# Adafruit_96x64_RGB_OLED_Breakout.net
KiCad netlist of a schematic drawn in EAGLE
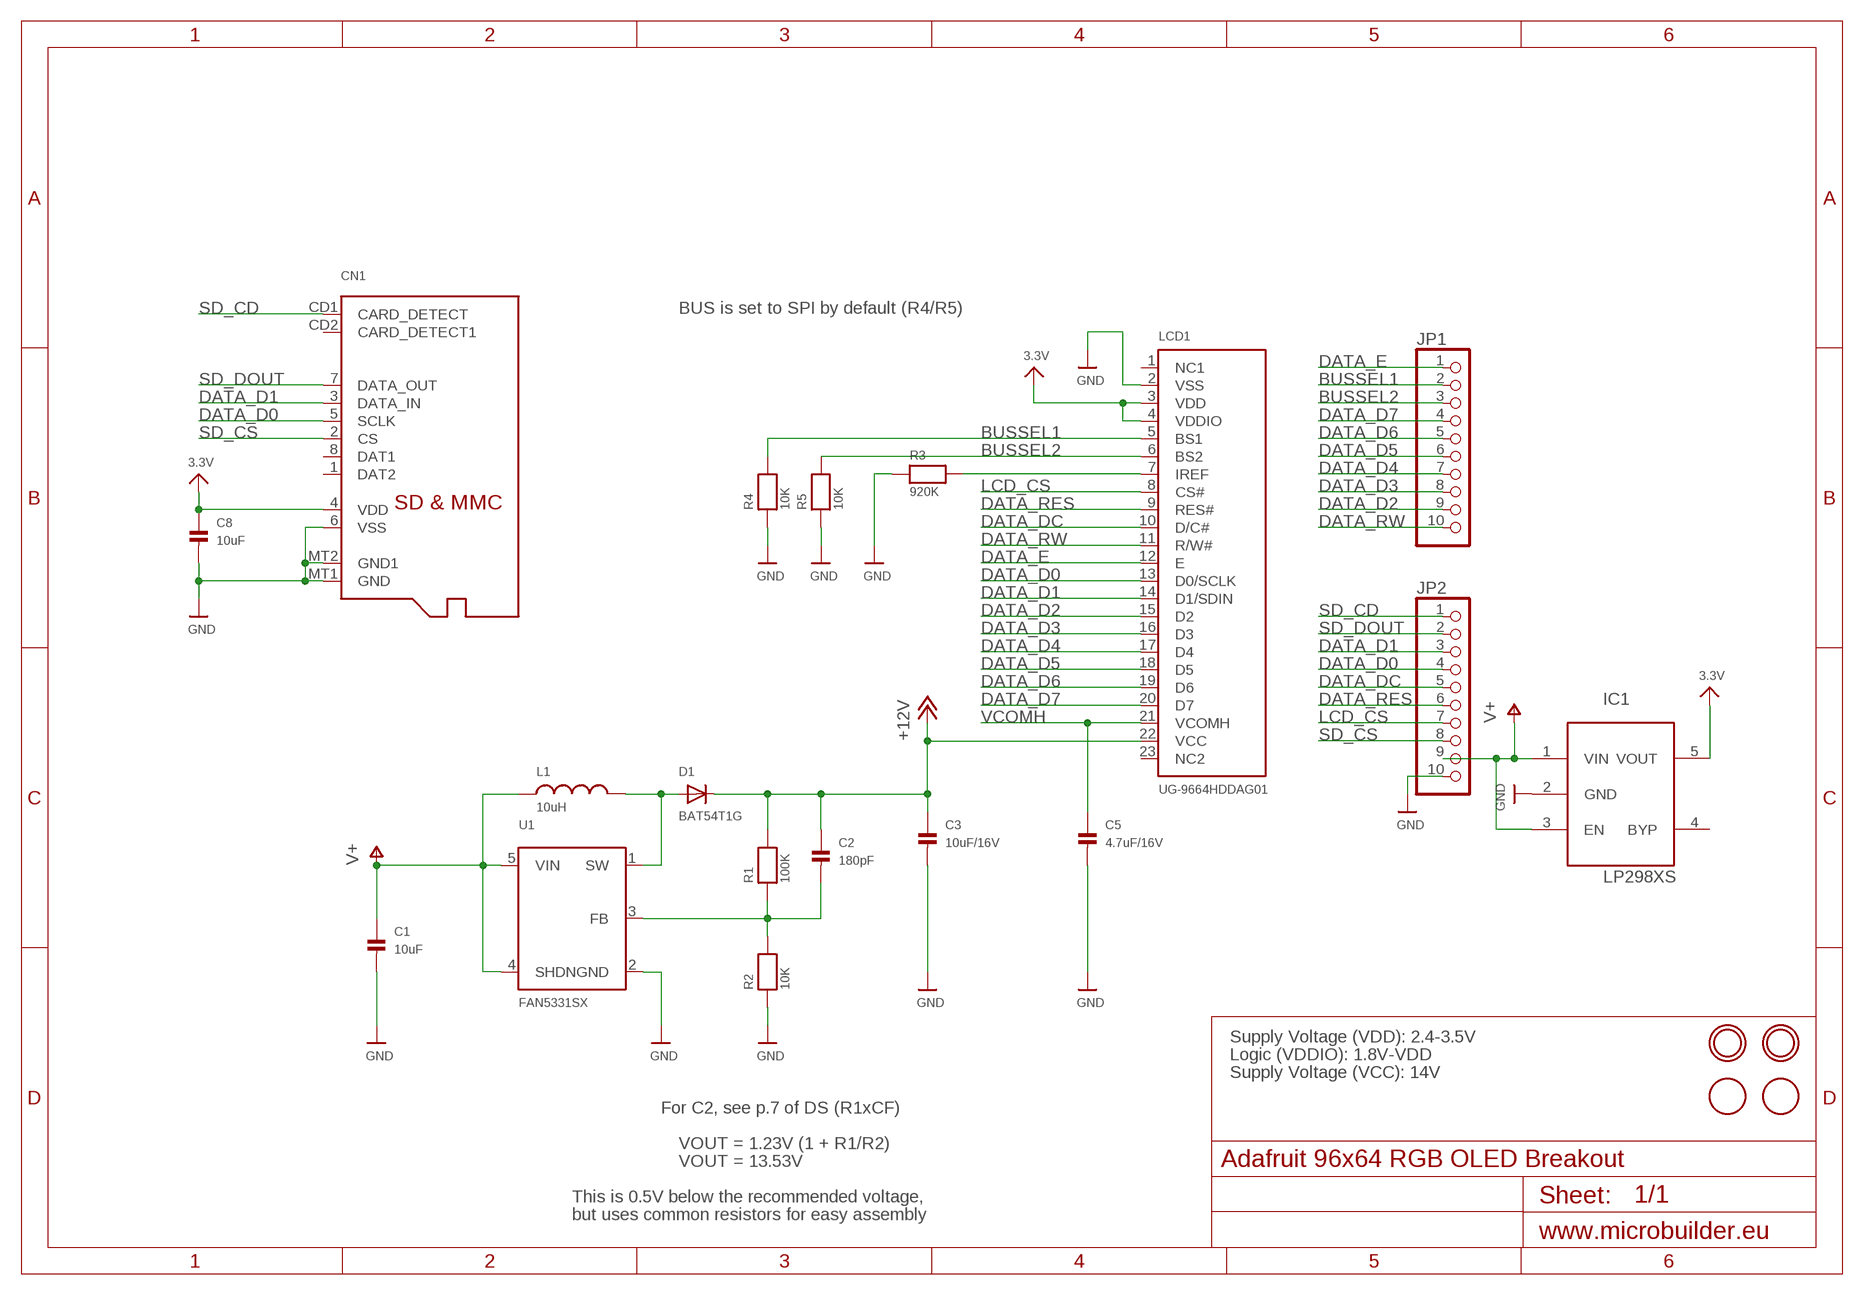
[diagram p0: schematic, sheet 1]

(export (version "E")
  (design (tool "Eeschema 10.0.6"))
  (components
    (comp (ref "C1")
      (value "10uF")
      (footprint "eagle-import:0805")
      (libsource (lib "eagle-import") (part "CAP_CERAMIC0805"))
    )
    (comp (ref "C2")
      (value "180pF")
      (footprint "eagle-import:0805")
      (libsource (lib "eagle-import") (part "CAP_CERAMIC0805"))
    )
    (comp (ref "C3")
      (value "10uF/16V")
      (footprint "eagle-import:0805")
      (libsource (lib "eagle-import") (part "CAP_CERAMIC0805"))
    )
    (comp (ref "C5")
      (value "4.7uF/16V")
      (footprint "eagle-import:0805")
      (libsource (lib "eagle-import") (part "CAP_CERAMIC0805"))
    )
    (comp (ref "C8")
      (value "10uF")
      (footprint "eagle-import:0805")
      (libsource (lib "eagle-import") (part "CAP_CERAMIC0805"))
    )
    (comp (ref "CN1")
      (value "MICROSD")
      (footprint "eagle-import:MICROSD")
      (libsource (lib "eagle-import") (part "MICROSD"))
    )
    (comp (ref "D1")
      (value "BAT54T1G")
      (footprint "eagle-import:SOD-123")
      (libsource (lib "eagle-import") (part "DIODESOD-123"))
    )
    (comp (ref "IC1")
      (value "LP298XS")
      (footprint "eagle-import:SOT23-5L")
      (libsource (lib "eagle-import") (part "LP298XS"))
    )
    (comp (ref "JP1")
      (value "HEADER-1X10THICKER")
      (footprint "eagle-import:1X10_ROUND_76")
      (libsource (lib "eagle-import") (part "HEADER-1X10THICKER"))
    )
    (comp (ref "JP2")
      (value "HEADER-1X10THICKER")
      (footprint "eagle-import:1X10_ROUND_76")
      (libsource (lib "eagle-import") (part "HEADER-1X10THICKER"))
    )
    (comp (ref "L1")
      (value "10uH")
      (footprint "eagle-import:INDUCTOR_1007")
      (libsource (lib "eagle-import") (part "INDUCTOR"))
    )
    (comp (ref "LCD1")
      (value "UG-9664HDDAG01")
      (footprint "eagle-import:UG-9664HDDAG01_WRAPAROUND")
      (libsource (lib "eagle-import") (part "OLED_UG-9664HDDAG01WRAPAROUND"))
    )
    (comp (ref "R1")
      (value "100K")
      (footprint "eagle-import:0805")
      (libsource (lib "eagle-import") (part "RESISTOR0805"))
    )
    (comp (ref "R2")
      (value "10K")
      (footprint "eagle-import:0805")
      (libsource (lib "eagle-import") (part "RESISTOR0805"))
    )
    (comp (ref "R3")
      (value "920K")
      (footprint "eagle-import:0805")
      (libsource (lib "eagle-import") (part "RESISTOR0805"))
    )
    (comp (ref "R4")
      (value "10K")
      (footprint "eagle-import:0805")
      (libsource (lib "eagle-import") (part "RESISTOR0805"))
    )
    (comp (ref "R5")
      (value "10K")
      (footprint "eagle-import:0805")
      (libsource (lib "eagle-import") (part "RESISTOR0805"))
    )
    (comp (ref "U$9")
      (value "MOUNTINGHOLE2.0")
      (footprint "eagle-import:MOUNTINGHOLE_2.0_PLATED")
      (libsource (lib "eagle-import") (part "MOUNTINGHOLE2.0"))
    )
    (comp (ref "U$11")
      (value "MOUNTINGHOLE2.0")
      (footprint "eagle-import:MOUNTINGHOLE_2.0_PLATED")
      (libsource (lib "eagle-import") (part "MOUNTINGHOLE2.0"))
    )
    (comp (ref "U$12")
      (value "FIDUCIAL")
      (footprint "eagle-import:FIDUCIAL_1MM")
      (libsource (lib "eagle-import") (part "FIDUCIAL"))
    )
    (comp (ref "U$13")
      (value "FIDUCIAL")
      (footprint "eagle-import:FIDUCIAL_1MM")
      (libsource (lib "eagle-import") (part "FIDUCIAL"))
    )
    (comp (ref "U1")
      (value "FAN5331SX")
      (footprint "eagle-import:SOT23-5")
      (libsource (lib "eagle-import") (part "FAN5331"))
    )
  )
  (nets
    (net (code "1") (name "+12V") (class "Default")
      (node (ref "C2") (pin "1") (pinfunction "P$1_1") (pintype "passive"))
      (node (ref "C3") (pin "1") (pinfunction "P$1_1") (pintype "passive"))
      (node (ref "D1") (pin "C") (pinfunction "C_C") (pintype "passive"))
      (node (ref "LCD1") (pin "22") (pinfunction "VCC_22") (pintype "bidirectional"))
      (node (ref "R1") (pin "2") (pinfunction "2_2") (pintype "passive"))
    )
    (net (code "2") (name "/BUSSEL1") (class "Default")
      (node (ref "JP1") (pin "2") (pinfunction "2_2") (pintype "passive"))
      (node (ref "LCD1") (pin "5") (pinfunction "BS1_5") (pintype "bidirectional"))
      (node (ref "R4") (pin "2") (pinfunction "2_2") (pintype "passive"))
    )
    (net (code "3") (name "/BUSSEL2") (class "Default")
      (node (ref "JP1") (pin "3") (pinfunction "3_3") (pintype "passive"))
      (node (ref "LCD1") (pin "6") (pinfunction "BS2_6") (pintype "bidirectional"))
      (node (ref "R5") (pin "2") (pinfunction "2_2") (pintype "passive"))
    )
    (net (code "4") (name "/DATA_D0") (class "Default")
      (node (ref "CN1") (pin "5") (pinfunction "SCLK_5") (pintype "input"))
      (node (ref "JP2") (pin "4") (pinfunction "4_4") (pintype "passive"))
      (node (ref "LCD1") (pin "13") (pinfunction "D0/SCLK_13") (pintype "bidirectional"))
    )
    (net (code "5") (name "/DATA_D1") (class "Default")
      (node (ref "CN1") (pin "3") (pinfunction "DATA_IN_3") (pintype "input"))
      (node (ref "JP2") (pin "3") (pinfunction "3_3") (pintype "passive"))
      (node (ref "LCD1") (pin "14") (pinfunction "D1/SDIN_14") (pintype "bidirectional"))
    )
    (net (code "6") (name "/DATA_D2") (class "Default")
      (node (ref "JP1") (pin "9") (pinfunction "9_9") (pintype "passive"))
      (node (ref "LCD1") (pin "15") (pinfunction "D2_15") (pintype "bidirectional"))
    )
    (net (code "7") (name "/DATA_D3") (class "Default")
      (node (ref "JP1") (pin "8") (pinfunction "8_8") (pintype "passive"))
      (node (ref "LCD1") (pin "16") (pinfunction "D3_16") (pintype "bidirectional"))
    )
    (net (code "8") (name "/DATA_D4") (class "Default")
      (node (ref "JP1") (pin "7") (pinfunction "7_7") (pintype "passive"))
      (node (ref "LCD1") (pin "17") (pinfunction "D4_17") (pintype "bidirectional"))
    )
    (net (code "9") (name "/DATA_D5") (class "Default")
      (node (ref "JP1") (pin "6") (pinfunction "6_6") (pintype "passive"))
      (node (ref "LCD1") (pin "18") (pinfunction "D5_18") (pintype "bidirectional"))
    )
    (net (code "10") (name "/DATA_D6") (class "Default")
      (node (ref "JP1") (pin "5") (pinfunction "5_5") (pintype "passive"))
      (node (ref "LCD1") (pin "19") (pinfunction "D6_19") (pintype "bidirectional"))
    )
    (net (code "11") (name "/DATA_D7") (class "Default")
      (node (ref "JP1") (pin "4") (pinfunction "4_4") (pintype "passive"))
      (node (ref "LCD1") (pin "20") (pinfunction "D7_20") (pintype "bidirectional"))
    )
    (net (code "12") (name "/DATA_DC") (class "Default")
      (node (ref "JP2") (pin "5") (pinfunction "5_5") (pintype "passive"))
      (node (ref "LCD1") (pin "10") (pinfunction "D/C#_10") (pintype "bidirectional"))
    )
    (net (code "13") (name "/DATA_E") (class "Default")
      (node (ref "JP1") (pin "1") (pinfunction "1_1") (pintype "passive"))
      (node (ref "LCD1") (pin "12") (pinfunction "E_12") (pintype "bidirectional"))
    )
    (net (code "14") (name "/DATA_RES") (class "Default")
      (node (ref "JP2") (pin "6") (pinfunction "6_6") (pintype "passive"))
      (node (ref "LCD1") (pin "9") (pinfunction "RES#_9") (pintype "bidirectional"))
    )
    (net (code "15") (name "/DATA_RW") (class "Default")
      (node (ref "JP1") (pin "10") (pinfunction "10_10") (pintype "passive"))
      (node (ref "LCD1") (pin "11") (pinfunction "R/W#_11") (pintype "bidirectional"))
    )
    (net (code "16") (name "/LCD_CS") (class "Default")
      (node (ref "JP2") (pin "7") (pinfunction "7_7") (pintype "passive"))
      (node (ref "LCD1") (pin "8") (pinfunction "CS#_8") (pintype "bidirectional"))
    )
    (net (code "17") (name "/SD_CD") (class "Default")
      (node (ref "CN1") (pin "CD1") (pinfunction "CARD_DETECT_CD1") (pintype "passive"))
      (node (ref "JP2") (pin "1") (pinfunction "1_1") (pintype "passive"))
    )
    (net (code "18") (name "/SD_CS") (class "Default")
      (node (ref "CN1") (pin "2") (pinfunction "CS_2") (pintype "input"))
      (node (ref "JP2") (pin "8") (pinfunction "8_8") (pintype "passive"))
    )
    (net (code "19") (name "/SD_DOUT") (class "Default")
      (node (ref "CN1") (pin "7") (pinfunction "DATA_OUT_7") (pintype "output"))
      (node (ref "JP2") (pin "2") (pinfunction "2_2") (pintype "passive"))
    )
    (net (code "20") (name "/VCOMH") (class "Default")
      (node (ref "C5") (pin "1") (pinfunction "P$1_1") (pintype "passive"))
      (node (ref "LCD1") (pin "21") (pinfunction "VCOMH_21") (pintype "bidirectional"))
    )
    (net (code "21") (name "3.3V") (class "Default")
      (node (ref "C8") (pin "1") (pinfunction "P$1_1") (pintype "passive"))
      (node (ref "CN1") (pin "4") (pinfunction "VDD_4") (pintype "power_in"))
      (node (ref "IC1") (pin "5") (pinfunction "VOUT_5") (pintype "bidirectional"))
      (node (ref "LCD1") (pin "3") (pinfunction "VDD_3") (pintype "bidirectional"))
      (node (ref "LCD1") (pin "4") (pinfunction "VDDIO_4") (pintype "bidirectional"))
    )
    (net (code "22") (name "GND") (class "Default")
      (node (ref "C1") (pin "2") (pinfunction "P$2_2") (pintype "passive"))
      (node (ref "C3") (pin "2") (pinfunction "P$2_2") (pintype "passive"))
      (node (ref "C5") (pin "2") (pinfunction "P$2_2") (pintype "passive"))
      (node (ref "C8") (pin "2") (pinfunction "P$2_2") (pintype "passive"))
      (node (ref "CN1") (pin "6") (pinfunction "VSS_6") (pintype "power_in"))
      (node (ref "CN1") (pin "MT1") (pinfunction "GND_MT1") (pintype "power_in"))
      (node (ref "CN1") (pin "MT2") (pinfunction "GND1_MT2") (pintype "power_in"))
      (node (ref "IC1") (pin "2") (pinfunction "GND_2") (pintype "bidirectional"))
      (node (ref "JP2") (pin "10") (pinfunction "10_10") (pintype "passive"))
      (node (ref "LCD1") (pin "2") (pinfunction "VSS_2") (pintype "bidirectional"))
      (node (ref "R2") (pin "1") (pinfunction "1_1") (pintype "passive"))
      (node (ref "R3") (pin "1") (pinfunction "1_1") (pintype "passive"))
      (node (ref "R4") (pin "1") (pinfunction "1_1") (pintype "passive"))
      (node (ref "R5") (pin "1") (pinfunction "1_1") (pintype "passive"))
      (node (ref "U1") (pin "2") (pinfunction "GND_2") (pintype "bidirectional"))
    )
    (net (code "23") (name "Net-(C2-P$2)") (class "Default")
      (node (ref "C2") (pin "2") (pinfunction "P$2_2") (pintype "passive"))
      (node (ref "R1") (pin "1") (pinfunction "1_1") (pintype "passive"))
      (node (ref "R2") (pin "2") (pinfunction "2_2") (pintype "passive"))
      (node (ref "U1") (pin "3") (pinfunction "FB_3") (pintype "bidirectional"))
    )
    (net (code "24") (name "Net-(L1-2)") (class "Default")
      (node (ref "D1") (pin "A") (pinfunction "A_A") (pintype "passive"))
      (node (ref "L1") (pin "P$2") (pinfunction "2_P$2") (pintype "passive"))
      (node (ref "U1") (pin "1") (pinfunction "SW_1") (pintype "bidirectional"))
    )
    (net (code "25") (name "Net-(LCD1-IREF)") (class "Default")
      (node (ref "LCD1") (pin "7") (pinfunction "IREF_7") (pintype "bidirectional"))
      (node (ref "R3") (pin "2") (pinfunction "2_2") (pintype "passive"))
    )
    (net (code "26") (name "V+") (class "Default")
      (node (ref "C1") (pin "1") (pinfunction "P$1_1") (pintype "passive"))
      (node (ref "IC1") (pin "1") (pinfunction "VIN_1") (pintype "bidirectional"))
      (node (ref "IC1") (pin "3") (pinfunction "EN_3") (pintype "bidirectional"))
      (node (ref "JP2") (pin "9") (pinfunction "9_9") (pintype "passive"))
      (node (ref "L1") (pin "P$1") (pinfunction "1_P$1") (pintype "passive"))
      (node (ref "U1") (pin "4") (pinfunction "SHDN_4") (pintype "bidirectional"))
      (node (ref "U1") (pin "5") (pinfunction "VIN_5") (pintype "bidirectional"))
    )
    (net (code "27") (name "unconnected-(CN1-CARD_DETECT1-PadCD2)") (class "Default")
      (node (ref "CN1") (pin "CD2") (pinfunction "CARD_DETECT1_CD2") (pintype "passive"))
    )
    (net (code "28") (name "unconnected-(CN1-DAT1-Pad8)") (class "Default")
      (node (ref "CN1") (pin "8") (pinfunction "DAT1_8") (pintype "bidirectional"))
    )
    (net (code "29") (name "unconnected-(CN1-DAT2-Pad1)") (class "Default")
      (node (ref "CN1") (pin "1") (pinfunction "DAT2_1") (pintype "bidirectional"))
    )
    (net (code "30") (name "unconnected-(IC1-BYP-Pad4)") (class "Default")
      (node (ref "IC1") (pin "4") (pinfunction "BYP_4") (pintype "bidirectional"))
    )
    (net (code "31") (name "unconnected-(LCD1-NC1-Pad1)") (class "Default")
      (node (ref "LCD1") (pin "1") (pinfunction "NC1_1") (pintype "no_connect"))
    )
    (net (code "32") (name "unconnected-(LCD1-NC2-Pad23)") (class "Default")
      (node (ref "LCD1") (pin "23") (pinfunction "NC2_23") (pintype "no_connect"))
    )
  )
)
